# adapter.net
KiCad netlist of a schematic drawn in EAGLE
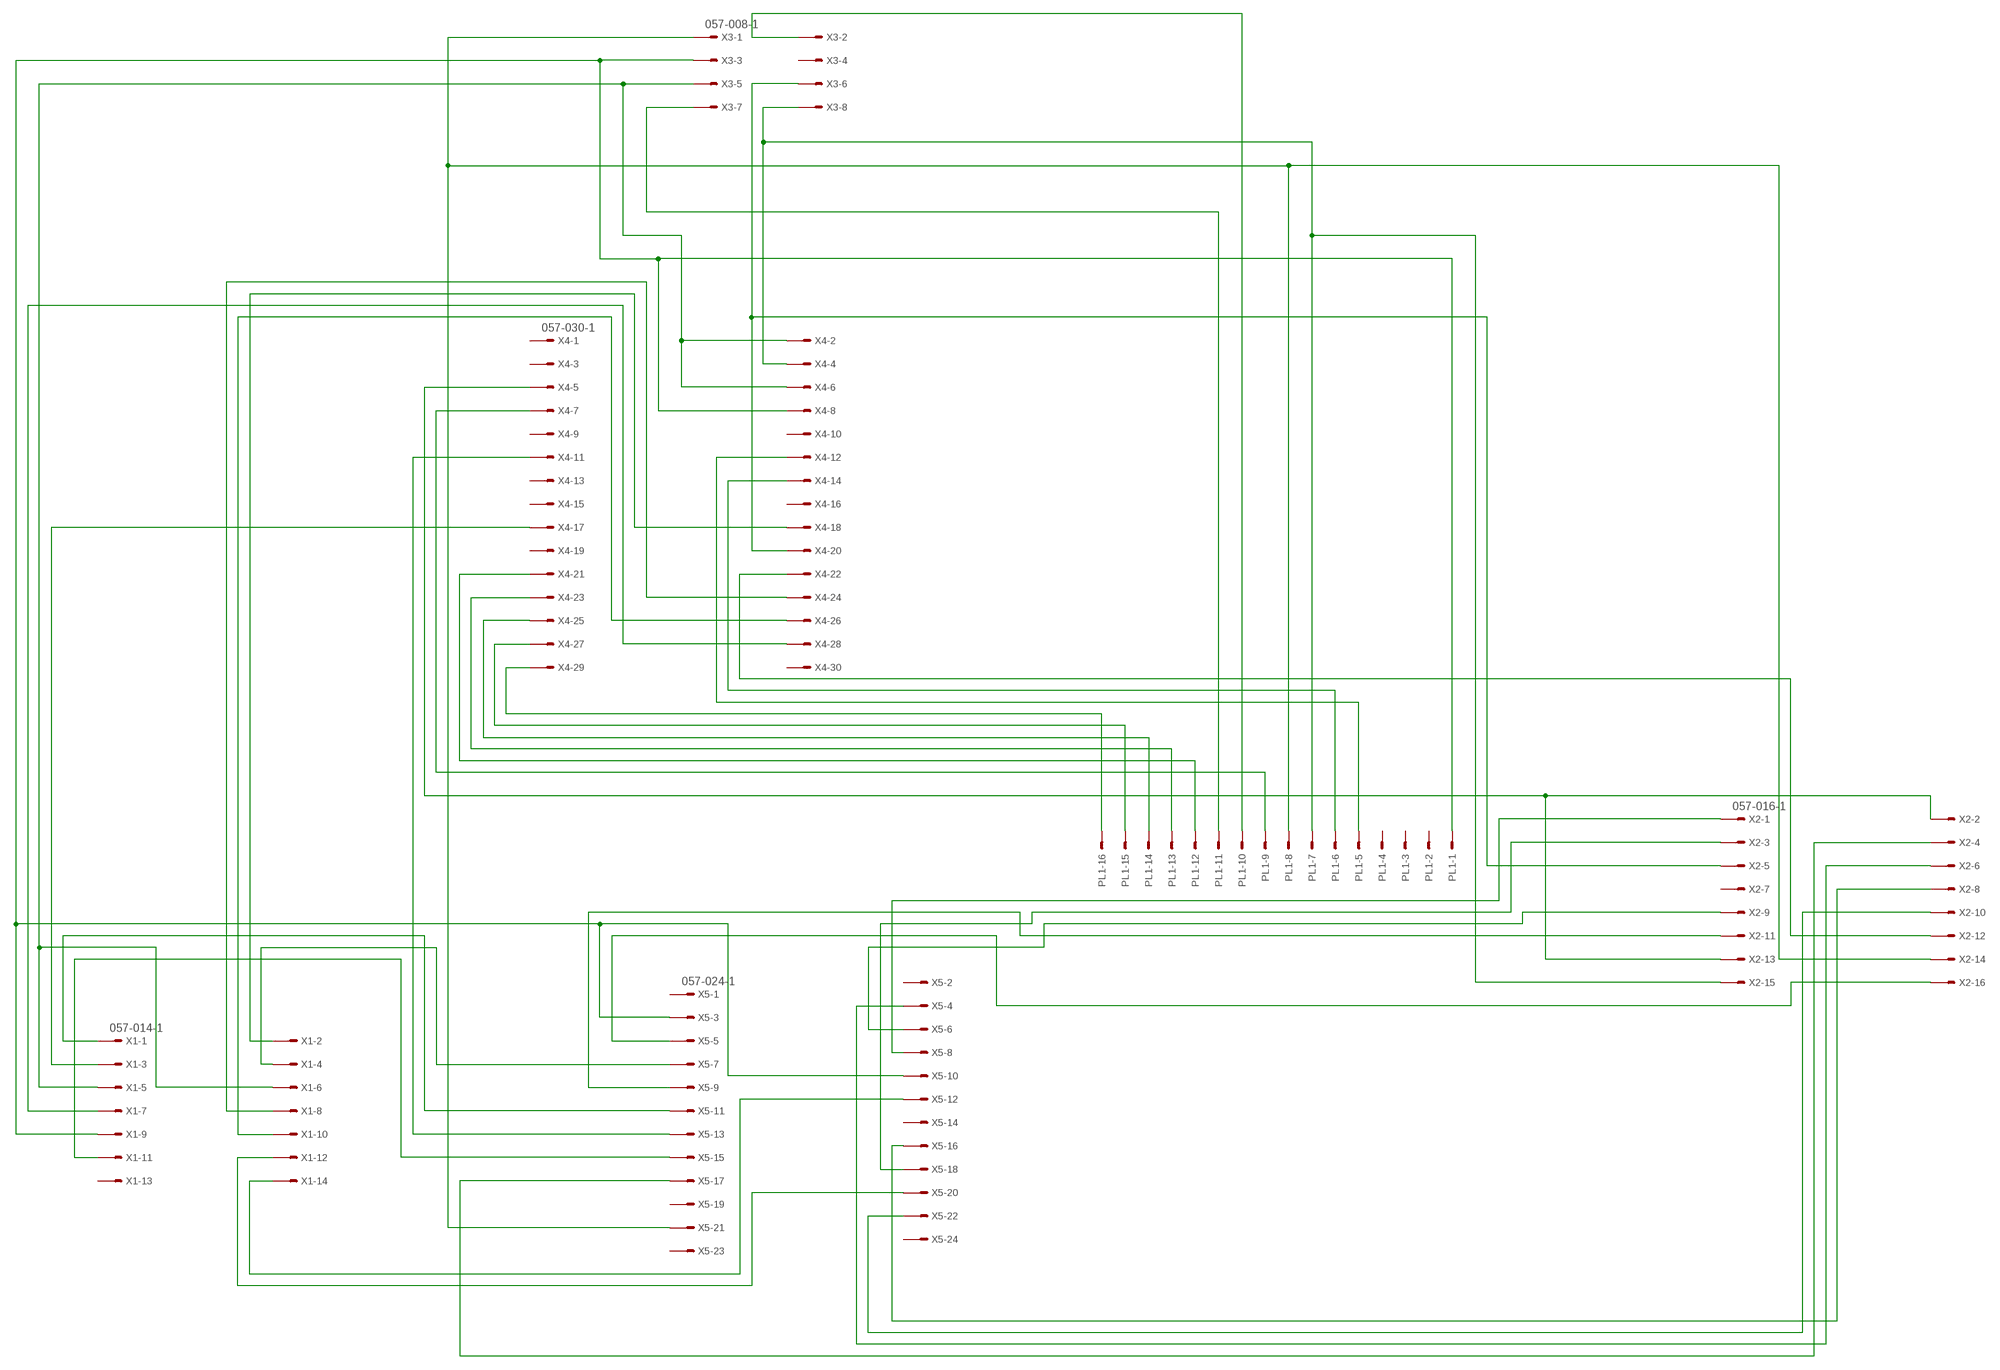
[diagram p0: schematic, sheet 1]

(export (version "E")
  (design (tool "Eeschema 10.0.6"))
  (components
    (comp (ref "PL1")
      (value "555X-16V")
      (footprint "eagle-import:5566-16")
      (libsource (lib "eagle-import") (part "555X-16V"))
    )
    (comp (ref "X1")
      (value "057-014-1")
      (footprint "eagle-import:057-014-1")
      (libsource (lib "eagle-import") (part "057-014-1"))
    )
    (comp (ref "X2")
      (value "057-016-1")
      (footprint "eagle-import:057-016-1")
      (libsource (lib "eagle-import") (part "057-016-1"))
    )
    (comp (ref "X3")
      (value "057-008-1")
      (footprint "eagle-import:057-008-1")
      (libsource (lib "eagle-import") (part "057-008-1"))
    )
    (comp (ref "X4")
      (value "057-030-1")
      (footprint "eagle-import:057-030-1")
      (libsource (lib "eagle-import") (part "057-030-1"))
    )
    (comp (ref "X5")
      (value "057-024-1")
      (footprint "eagle-import:057-024-1")
      (libsource (lib "eagle-import") (part "057-024-1"))
    )
  )
  (nets
    (net (code "1") (name "Net-(PL1A-S)") (class "Default")
      (node (ref "PL1") (pin "1") (pinfunction "S_1") (pintype "passive"))
      (node (ref "X1") (pin "9") (pinfunction "S_9") (pintype "passive"))
      (node (ref "X3") (pin "3") (pinfunction "S_3") (pintype "passive"))
      (node (ref "X4") (pin "8") (pinfunction "S_8") (pintype "passive"))
      (node (ref "X5") (pin "10") (pinfunction "S_10") (pintype "passive"))
      (node (ref "X5") (pin "3") (pinfunction "S_3") (pintype "passive"))
    )
    (net (code "2") (name "Net-(PL1B-S)") (class "Default")
      (node (ref "PL1") (pin "10") (pinfunction "S_10") (pintype "passive"))
      (node (ref "X3") (pin "2") (pinfunction "S_2") (pintype "passive"))
    )
    (net (code "3") (name "Net-(PL1C-S)") (class "Default")
      (node (ref "PL1") (pin "11") (pinfunction "S_11") (pintype "passive"))
      (node (ref "X3") (pin "7") (pinfunction "S_7") (pintype "passive"))
    )
    (net (code "4") (name "Net-(PL1D-S)") (class "Default")
      (node (ref "PL1") (pin "12") (pinfunction "S_12") (pintype "passive"))
      (node (ref "X4") (pin "21") (pinfunction "S_21") (pintype "passive"))
    )
    (net (code "5") (name "Net-(PL1E-S)") (class "Default")
      (node (ref "PL1") (pin "13") (pinfunction "S_13") (pintype "passive"))
      (node (ref "X4") (pin "23") (pinfunction "S_23") (pintype "passive"))
    )
    (net (code "6") (name "Net-(PL1F-S)") (class "Default")
      (node (ref "PL1") (pin "14") (pinfunction "S_14") (pintype "passive"))
      (node (ref "X4") (pin "25") (pinfunction "S_25") (pintype "passive"))
    )
    (net (code "7") (name "Net-(PL1G-S)") (class "Default")
      (node (ref "PL1") (pin "15") (pinfunction "S_15") (pintype "passive"))
      (node (ref "X4") (pin "27") (pinfunction "S_27") (pintype "passive"))
    )
    (net (code "8") (name "Net-(PL1H-S)") (class "Default")
      (node (ref "PL1") (pin "16") (pinfunction "S_16") (pintype "passive"))
      (node (ref "X4") (pin "29") (pinfunction "S_29") (pintype "passive"))
    )
    (net (code "9") (name "Net-(PL1L-S)") (class "Default")
      (node (ref "PL1") (pin "5") (pinfunction "S_5") (pintype "passive"))
      (node (ref "X4") (pin "12") (pinfunction "S_12") (pintype "passive"))
    )
    (net (code "10") (name "Net-(PL1M-S)") (class "Default")
      (node (ref "PL1") (pin "6") (pinfunction "S_6") (pintype "passive"))
      (node (ref "X4") (pin "14") (pinfunction "S_14") (pintype "passive"))
    )
    (net (code "11") (name "Net-(PL1N-S)") (class "Default")
      (node (ref "PL1") (pin "7") (pinfunction "S_7") (pintype "passive"))
      (node (ref "X2") (pin "15") (pinfunction "S_15") (pintype "passive"))
      (node (ref "X3") (pin "8") (pinfunction "S_8") (pintype "passive"))
      (node (ref "X4") (pin "4") (pinfunction "S_4") (pintype "passive"))
    )
    (net (code "12") (name "Net-(PL1O-S)") (class "Default")
      (node (ref "PL1") (pin "8") (pinfunction "S_8") (pintype "passive"))
      (node (ref "X2") (pin "14") (pinfunction "S_14") (pintype "passive"))
      (node (ref "X3") (pin "1") (pinfunction "S_1") (pintype "passive"))
      (node (ref "X5") (pin "21") (pinfunction "S_21") (pintype "passive"))
    )
    (net (code "13") (name "Net-(PL1P-S)") (class "Default")
      (node (ref "PL1") (pin "9") (pinfunction "S_9") (pintype "passive"))
      (node (ref "X4") (pin "7") (pinfunction "S_7") (pintype "passive"))
    )
    (net (code "14") (name "Net-(X1A-S)") (class "Default")
      (node (ref "X1") (pin "1") (pinfunction "S_1") (pintype "passive"))
      (node (ref "X5") (pin "11") (pinfunction "S_11") (pintype "passive"))
    )
    (net (code "15") (name "Net-(X1B-S)") (class "Default")
      (node (ref "X1") (pin "10") (pinfunction "S_10") (pintype "passive"))
      (node (ref "X4") (pin "26") (pinfunction "S_26") (pintype "passive"))
    )
    (net (code "16") (name "Net-(X1C-S)") (class "Default")
      (node (ref "X1") (pin "11") (pinfunction "S_11") (pintype "passive"))
      (node (ref "X5") (pin "15") (pinfunction "S_15") (pintype "passive"))
    )
    (net (code "17") (name "Net-(X1D-S)") (class "Default")
      (node (ref "X1") (pin "12") (pinfunction "S_12") (pintype "passive"))
      (node (ref "X5") (pin "20") (pinfunction "S_20") (pintype "passive"))
    )
    (net (code "18") (name "Net-(X1F-S)") (class "Default")
      (node (ref "X1") (pin "14") (pinfunction "S_14") (pintype "passive"))
      (node (ref "X5") (pin "12") (pinfunction "S_12") (pintype "passive"))
    )
    (net (code "19") (name "Net-(X1G-S)") (class "Default")
      (node (ref "X1") (pin "2") (pinfunction "S_2") (pintype "passive"))
      (node (ref "X4") (pin "18") (pinfunction "S_18") (pintype "passive"))
    )
    (net (code "20") (name "Net-(X1H-S)") (class "Default")
      (node (ref "X1") (pin "3") (pinfunction "S_3") (pintype "passive"))
      (node (ref "X4") (pin "17") (pinfunction "S_17") (pintype "passive"))
    )
    (net (code "21") (name "Net-(X1I-S)") (class "Default")
      (node (ref "X1") (pin "4") (pinfunction "S_4") (pintype "passive"))
      (node (ref "X5") (pin "7") (pinfunction "S_7") (pintype "passive"))
    )
    (net (code "22") (name "Net-(X1J-S)") (class "Default")
      (node (ref "X1") (pin "5") (pinfunction "S_5") (pintype "passive"))
      (node (ref "X1") (pin "6") (pinfunction "S_6") (pintype "passive"))
      (node (ref "X3") (pin "5") (pinfunction "S_5") (pintype "passive"))
      (node (ref "X4") (pin "2") (pinfunction "S_2") (pintype "passive"))
      (node (ref "X4") (pin "6") (pinfunction "S_6") (pintype "passive"))
    )
    (net (code "23") (name "Net-(X1L-S)") (class "Default")
      (node (ref "X1") (pin "7") (pinfunction "S_7") (pintype "passive"))
      (node (ref "X4") (pin "28") (pinfunction "S_28") (pintype "passive"))
    )
    (net (code "24") (name "Net-(X1M-S)") (class "Default")
      (node (ref "X1") (pin "8") (pinfunction "S_8") (pintype "passive"))
      (node (ref "X4") (pin "24") (pinfunction "S_24") (pintype "passive"))
    )
    (net (code "25") (name "Net-(X2A-S)") (class "Default")
      (node (ref "X2") (pin "1") (pinfunction "S_1") (pintype "passive"))
      (node (ref "X5") (pin "8") (pinfunction "S_8") (pintype "passive"))
    )
    (net (code "26") (name "Net-(X2B-S)") (class "Default")
      (node (ref "X2") (pin "10") (pinfunction "S_10") (pintype "passive"))
      (node (ref "X5") (pin "22") (pinfunction "S_22") (pintype "passive"))
    )
    (net (code "27") (name "Net-(X2C-S)") (class "Default")
      (node (ref "X2") (pin "11") (pinfunction "S_11") (pintype "passive"))
      (node (ref "X5") (pin "9") (pinfunction "S_9") (pintype "passive"))
    )
    (net (code "28") (name "Net-(X2D-S)") (class "Default")
      (node (ref "X2") (pin "12") (pinfunction "S_12") (pintype "passive"))
      (node (ref "X4") (pin "22") (pinfunction "S_22") (pintype "passive"))
    )
    (net (code "29") (name "Net-(X2E-S)") (class "Default")
      (node (ref "X2") (pin "13") (pinfunction "S_13") (pintype "passive"))
      (node (ref "X2") (pin "2") (pinfunction "S_2") (pintype "passive"))
      (node (ref "X4") (pin "5") (pinfunction "S_5") (pintype "passive"))
    )
    (net (code "30") (name "Net-(X2H-S)") (class "Default")
      (node (ref "X2") (pin "16") (pinfunction "S_16") (pintype "passive"))
      (node (ref "X5") (pin "5") (pinfunction "S_5") (pintype "passive"))
    )
    (net (code "31") (name "Net-(X2J-S)") (class "Default")
      (node (ref "X2") (pin "3") (pinfunction "S_3") (pintype "passive"))
      (node (ref "X5") (pin "18") (pinfunction "S_18") (pintype "passive"))
    )
    (net (code "32") (name "Net-(X2K-S)") (class "Default")
      (node (ref "X2") (pin "4") (pinfunction "S_4") (pintype "passive"))
      (node (ref "X5") (pin "17") (pinfunction "S_17") (pintype "passive"))
    )
    (net (code "33") (name "Net-(X2L-S)") (class "Default")
      (node (ref "X2") (pin "5") (pinfunction "S_5") (pintype "passive"))
      (node (ref "X3") (pin "6") (pinfunction "S_6") (pintype "passive"))
      (node (ref "X4") (pin "20") (pinfunction "S_20") (pintype "passive"))
    )
    (net (code "34") (name "Net-(X2M-S)") (class "Default")
      (node (ref "X2") (pin "6") (pinfunction "S_6") (pintype "passive"))
      (node (ref "X5") (pin "4") (pinfunction "S_4") (pintype "passive"))
    )
    (net (code "35") (name "Net-(X2O-S)") (class "Default")
      (node (ref "X2") (pin "8") (pinfunction "S_8") (pintype "passive"))
      (node (ref "X5") (pin "16") (pinfunction "S_16") (pintype "passive"))
    )
    (net (code "36") (name "Net-(X2P-S)") (class "Default")
      (node (ref "X2") (pin "9") (pinfunction "S_9") (pintype "passive"))
      (node (ref "X5") (pin "6") (pinfunction "S_6") (pintype "passive"))
    )
    (net (code "37") (name "Net-(X4C-S)") (class "Default")
      (node (ref "X4") (pin "11") (pinfunction "S_11") (pintype "passive"))
      (node (ref "X5") (pin "13") (pinfunction "S_13") (pintype "passive"))
    )
    (net (code "38") (name "unconnected-(PL1I-S-Pad2)") (class "Default")
      (node (ref "PL1") (pin "2") (pinfunction "S_2") (pintype "passive"))
    )
    (net (code "39") (name "unconnected-(PL1J-S-Pad3)") (class "Default")
      (node (ref "PL1") (pin "3") (pinfunction "S_3") (pintype "passive"))
    )
    (net (code "40") (name "unconnected-(PL1K-S-Pad4)") (class "Default")
      (node (ref "PL1") (pin "4") (pinfunction "S_4") (pintype "passive"))
    )
    (net (code "41") (name "unconnected-(X1E-S-Pad13)") (class "Default")
      (node (ref "X1") (pin "13") (pinfunction "S_13") (pintype "passive"))
    )
    (net (code "42") (name "unconnected-(X2N-S-Pad7)") (class "Default")
      (node (ref "X2") (pin "7") (pinfunction "S_7") (pintype "passive"))
    )
    (net (code "43") (name "unconnected-(X3D-S-Pad4)") (class "Default")
      (node (ref "X3") (pin "4") (pinfunction "S_4") (pintype "passive"))
    )
    (net (code "44") (name "unconnected-(X4A-S-Pad1)") (class "Default")
      (node (ref "X4") (pin "1") (pinfunction "S_1") (pintype "passive"))
    )
    (net (code "45") (name "unconnected-(X4AD-S-Pad9)") (class "Default")
      (node (ref "X4") (pin "9") (pinfunction "S_9") (pintype "passive"))
    )
    (net (code "46") (name "unconnected-(X4B-S-Pad10)") (class "Default")
      (node (ref "X4") (pin "10") (pinfunction "S_10") (pintype "passive"))
    )
    (net (code "47") (name "unconnected-(X4E-S-Pad13)") (class "Default")
      (node (ref "X4") (pin "13") (pinfunction "S_13") (pintype "passive"))
    )
    (net (code "48") (name "unconnected-(X4G-S-Pad15)") (class "Default")
      (node (ref "X4") (pin "15") (pinfunction "S_15") (pintype "passive"))
    )
    (net (code "49") (name "unconnected-(X4H-S-Pad16)") (class "Default")
      (node (ref "X4") (pin "16") (pinfunction "S_16") (pintype "passive"))
    )
    (net (code "50") (name "unconnected-(X4K-S-Pad19)") (class "Default")
      (node (ref "X4") (pin "19") (pinfunction "S_19") (pintype "passive"))
    )
    (net (code "51") (name "unconnected-(X4W-S-Pad3)") (class "Default")
      (node (ref "X4") (pin "3") (pinfunction "S_3") (pintype "passive"))
    )
    (net (code "52") (name "unconnected-(X4X-S-Pad30)") (class "Default")
      (node (ref "X4") (pin "30") (pinfunction "S_30") (pintype "passive"))
    )
    (net (code "53") (name "unconnected-(X5A-S-Pad1)") (class "Default")
      (node (ref "X5") (pin "1") (pinfunction "S_1") (pintype "passive"))
    )
    (net (code "54") (name "unconnected-(X5F-S-Pad14)") (class "Default")
      (node (ref "X5") (pin "14") (pinfunction "S_14") (pintype "passive"))
    )
    (net (code "55") (name "unconnected-(X5K-S-Pad19)") (class "Default")
      (node (ref "X5") (pin "19") (pinfunction "S_19") (pintype "passive"))
    )
    (net (code "56") (name "unconnected-(X5L-S-Pad2)") (class "Default")
      (node (ref "X5") (pin "2") (pinfunction "S_2") (pintype "passive"))
    )
    (net (code "57") (name "unconnected-(X5P-S-Pad23)") (class "Default")
      (node (ref "X5") (pin "23") (pinfunction "S_23") (pintype "passive"))
    )
    (net (code "58") (name "unconnected-(X5Q-S-Pad24)") (class "Default")
      (node (ref "X5") (pin "24") (pinfunction "S_24") (pintype "passive"))
    )
  )
)
